# 01_MCU_DSP.net
KiCad netlist of a schematic drawn in Altium Designer
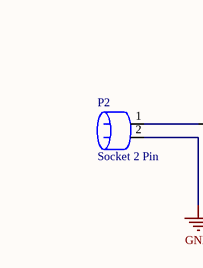
[diagram p0: 01_MCU_DSP..SchDoc, bottom left]
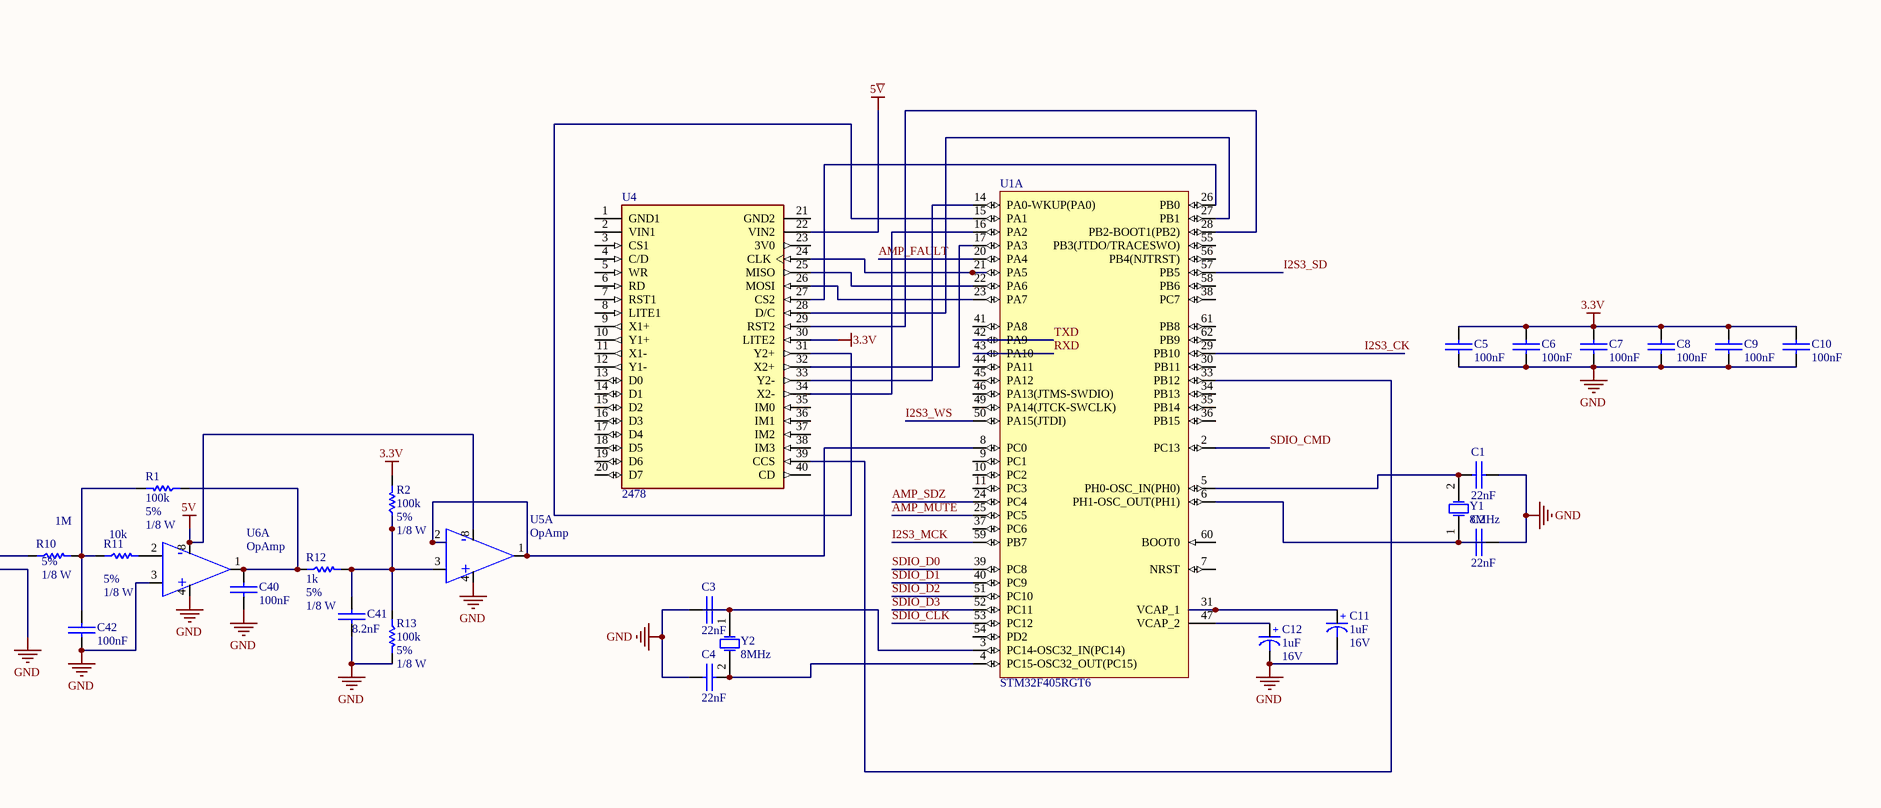
[diagram p1: 01_MCU_DSP..SchDoc, bottom right]

(export (version "E")
  (design (tool "Eeschema 10.0.6"))
  (components
    (comp (ref "C1")
      (value "22nF")
      (footprint "SMD_CAP_1206")
      (description "Bipolar Capacitor")
      (fields (field (name "VOLTAGE") "100V") (field (name "DESIGNER") "Saeid Jorablo"))
      (libsource (lib "My Library") (part "Cap-Bipolar"))
    )
    (comp (ref "C2")
      (value "22nF")
      (footprint "SMD_CAP_1206")
      (description "Bipolar Capacitor")
      (fields (field (name "VOLTAGE") "100V") (field (name "DESIGNER") "Saeid Jorablo"))
      (libsource (lib "My Library") (part "Cap-Bipolar"))
    )
    (comp (ref "C3")
      (value "22nF")
      (footprint "SMD_CAP_1206")
      (description "Bipolar Capacitor")
      (fields (field (name "VOLTAGE") "100V") (field (name "DESIGNER") "Saeid Jorablo"))
      (libsource (lib "My Library") (part "Cap-Bipolar"))
    )
    (comp (ref "C4")
      (value "22nF")
      (footprint "SMD_CAP_1206")
      (description "Bipolar Capacitor")
      (fields (field (name "VOLTAGE") "100V") (field (name "DESIGNER") "Saeid Jorablo"))
      (libsource (lib "My Library") (part "Cap-Bipolar"))
    )
    (comp (ref "C5")
      (value "100nF")
      (footprint "SMD_CAP_1206")
      (description "Bipolar Capacitor")
      (fields (field (name "VOLTAGE") "100V") (field (name "DESIGNER") "Saeid Jorablo"))
      (libsource (lib "My Library") (part "Cap-Bipolar"))
    )
    (comp (ref "C6")
      (value "100nF")
      (footprint "SMD_CAP_1206")
      (description "Bipolar Capacitor")
      (fields (field (name "VOLTAGE") "100V") (field (name "DESIGNER") "Saeid Jorablo"))
      (libsource (lib "My Library") (part "Cap-Bipolar"))
    )
    (comp (ref "C7")
      (value "100nF")
      (footprint "SMD_CAP_1206")
      (description "Bipolar Capacitor")
      (fields (field (name "VOLTAGE") "100V") (field (name "DESIGNER") "Saeid Jorablo"))
      (libsource (lib "My Library") (part "Cap-Bipolar"))
    )
    (comp (ref "C8")
      (value "100nF")
      (footprint "SMD_CAP_1206")
      (description "Bipolar Capacitor")
      (fields (field (name "VOLTAGE") "100V") (field (name "DESIGNER") "Saeid Jorablo"))
      (libsource (lib "My Library") (part "Cap-Bipolar"))
    )
    (comp (ref "C9")
      (value "100nF")
      (footprint "SMD_CAP_1206")
      (description "Bipolar Capacitor")
      (fields (field (name "VOLTAGE") "100V") (field (name "DESIGNER") "Saeid Jorablo"))
      (libsource (lib "My Library") (part "Cap-Bipolar"))
    )
    (comp (ref "C10")
      (value "100nF")
      (footprint "SMD_CAP_1206")
      (description "Bipolar Capacitor")
      (fields (field (name "VOLTAGE") "100V") (field (name "DESIGNER") "Saeid Jorablo"))
      (libsource (lib "My Library") (part "Cap-Bipolar"))
    )
    (comp (ref "C11")
      (value "1uF")
      (footprint "cap 01")
      (description "Polar Capacitor")
      (fields (field (name "VOLTAGE") "16V") (field (name "DESIGNER") "Saeid Jorablo"))
      (libsource (lib "My Library") (part "Cap-Polar"))
    )
    (comp (ref "C12")
      (value "1uF")
      (footprint "cap 01")
      (description "Polar Capacitor")
      (fields (field (name "VOLTAGE") "16V") (field (name "DESIGNER") "Saeid Jorablo"))
      (libsource (lib "My Library") (part "Cap-Polar"))
    )
    (comp (ref "C40")
      (value "100nF")
      (footprint "SMD_CAP_1206")
      (description "Bipolar Capacitor")
      (fields (field (name "VOLTAGE") "100V") (field (name "DESIGNER") "Saeid Jorablo"))
      (libsource (lib "My Library") (part "Cap-Bipolar"))
    )
    (comp (ref "C41")
      (value "8.2nF")
      (footprint "SMD_CAP_1206")
      (description "Bipolar Capacitor")
      (fields (field (name "VOLTAGE") "100V") (field (name "DESIGNER") "Saeid Jorablo"))
      (libsource (lib "My Library") (part "Cap-Bipolar"))
    )
    (comp (ref "C42")
      (value "100nF")
      (footprint "SMD_CAP_1206")
      (description "Bipolar Capacitor")
      (fields (field (name "VOLTAGE") "100V") (field (name "DESIGNER") "Saeid Jorablo"))
      (libsource (lib "My Library") (part "Cap-Bipolar"))
    )
    (comp (ref "P2")
      (value "Socket 2 Pin")
      (footprint "2pin")
      (description "Power Input")
      (libsource (lib "My Library") (part "Socket 2 Pin"))
    )
    (comp (ref "R1")
      (value "100k")
      (footprint "RES 0805 (2012X06L)")
      (description "Resistor")
      (fields (field (name "TOLERANCE") "5%") (field (name "POWER") "1/8 W"))
      (libsource (lib "My Library") (part "Resistor"))
    )
    (comp (ref "R2")
      (value "100k")
      (footprint "RES 0805 (2012X06L)")
      (description "Resistor")
      (fields (field (name "TOLERANCE") "5%") (field (name "POWER") "1/8 W"))
      (libsource (lib "My Library") (part "Resistor"))
    )
    (comp (ref "R10")
      (value "1M")
      (footprint "RES 0805 (2012X06L)")
      (description "Resistor")
      (fields (field (name "TOLERANCE") "5%") (field (name "POWER") "1/8 W"))
      (libsource (lib "My Library") (part "Resistor"))
    )
    (comp (ref "R11")
      (value "10k")
      (footprint "RES 0805 (2012X06L)")
      (description "Resistor")
      (fields (field (name "TOLERANCE") "5%") (field (name "POWER") "1/8 W"))
      (libsource (lib "My Library") (part "Resistor"))
    )
    (comp (ref "R12")
      (value "1k")
      (footprint "RES 0805 (2012X06L)")
      (description "Resistor")
      (fields (field (name "TOLERANCE") "5%") (field (name "POWER") "1/8 W"))
      (libsource (lib "My Library") (part "Resistor"))
    )
    (comp (ref "R13")
      (value "100k")
      (footprint "RES 0805 (2012X06L)")
      (description "Resistor")
      (fields (field (name "TOLERANCE") "5%") (field (name "POWER") "1/8 W"))
      (libsource (lib "My Library") (part "Resistor"))
    )
    (comp (ref "U1")
      (value "STM32F405RGT6")
      (footprint "STM-LQFP64_N")
      (fields (field (name "MANUFACTURER") "STMicroelectronics"))
      (libsource (lib "STMicroelectronics STM32 F4") (part "STM32F405RGT6"))
    )
    (comp (ref "U4")
      (value "2478")
      (footprint "ADAFRUIT_2478")
      (fields (field (name "MF") "Adafruit Industries"))
      (libsource (lib "2478") (part "2478"))
    )
    (comp (ref "U5")
      (value "OpAmp")
      (footprint "SOIC8-Narrow")
      (description "Dual Low Noise Operational Amplifier (OpAmp)")
      (libsource (lib "My Library") (part "OpAmp"))
    )
    (comp (ref "U6")
      (value "OpAmp")
      (footprint "SOIC8-Narrow")
      (description "Dual Low Noise Operational Amplifier (OpAmp)")
      (libsource (lib "My Library") (part "OpAmp"))
    )
    (comp (ref "Y1")
      (value "8MHz")
      (footprint "XTAL Small")
      (description "XTAL Crystal")
      (libsource (lib "My Library") (part "XTAL"))
    )
    (comp (ref "Y2")
      (value "8MHz")
      (footprint "XTAL Small")
      (description "XTAL Crystal")
      (libsource (lib "My Library") (part "XTAL"))
    )
  )
  (nets
    (net (code "1") (name "/AMP_FAULT") (class "Default")
      (node (ref "U1") (pin "20") (pinfunction "PA4_20") (pintype "bidirectional"))
    )
    (net (code "2") (name "/AMP_MUTE") (class "Default")
      (node (ref "U1") (pin "25") (pinfunction "PC5_25") (pintype "bidirectional"))
    )
    (net (code "3") (name "/AMP_SDZ") (class "Default")
      (node (ref "U1") (pin "24") (pinfunction "PC4_24") (pintype "bidirectional"))
    )
    (net (code "4") (name "/I2S3_CK") (class "Default")
      (node (ref "U1") (pin "29") (pinfunction "PB10_29") (pintype "bidirectional"))
    )
    (net (code "5") (name "/I2S3_MCK") (class "Default")
      (node (ref "U1") (pin "59") (pinfunction "PB7_59") (pintype "bidirectional"))
    )
    (net (code "6") (name "/I2S3_SD") (class "Default")
      (node (ref "U1") (pin "57") (pinfunction "PB5_57") (pintype "bidirectional"))
    )
    (net (code "7") (name "/I2S3_WS") (class "Default")
      (node (ref "U1") (pin "50") (pinfunction "PA15(JTDI)_50") (pintype "bidirectional"))
    )
    (net (code "8") (name "/RXD") (class "Default")
      (node (ref "U1") (pin "43") (pinfunction "PA10_43") (pintype "bidirectional"))
    )
    (net (code "9") (name "/SDIO_CLK") (class "Default")
      (node (ref "U1") (pin "53") (pinfunction "PC12_53") (pintype "bidirectional"))
    )
    (net (code "10") (name "/SDIO_CMD") (class "Default")
      (node (ref "U1") (pin "2") (pinfunction "PC13_2") (pintype "bidirectional"))
    )
    (net (code "11") (name "/SDIO_D0") (class "Default")
      (node (ref "U1") (pin "39") (pinfunction "PC8_39") (pintype "bidirectional"))
    )
    (net (code "12") (name "/SDIO_D1") (class "Default")
      (node (ref "U1") (pin "40") (pinfunction "PC9_40") (pintype "bidirectional"))
    )
    (net (code "13") (name "/SDIO_D2") (class "Default")
      (node (ref "U1") (pin "51") (pinfunction "PC10_51") (pintype "bidirectional"))
    )
    (net (code "14") (name "/SDIO_D3") (class "Default")
      (node (ref "U1") (pin "52") (pinfunction "PC11_52") (pintype "bidirectional"))
    )
    (net (code "15") (name "/TXD") (class "Default")
      (node (ref "U1") (pin "42") (pinfunction "PA9_42") (pintype "bidirectional"))
    )
    (net (code "16") (name "3.3V") (class "Default")
      (node (ref "C10") (pin "1") (pinfunction "+_1") (pintype "passive"))
      (node (ref "C5") (pin "1") (pinfunction "+_1") (pintype "passive"))
      (node (ref "C6") (pin "1") (pinfunction "+_1") (pintype "passive"))
      (node (ref "C7") (pin "1") (pinfunction "+_1") (pintype "passive"))
      (node (ref "C8") (pin "1") (pinfunction "+_1") (pintype "passive"))
      (node (ref "C9") (pin "1") (pinfunction "+_1") (pintype "passive"))
      (node (ref "R2") (pin "2") (pinfunction "2_2") (pintype "passive"))
      (node (ref "U4") (pin "30") (pinfunction "LITE2_30") (pintype "input"))
    )
    (net (code "17") (name "5V") (class "Default")
      (node (ref "U5") (pin "8") (pinfunction "V+_8") (pintype "passive"))
      (node (ref "U6") (pin "8") (pinfunction "V+_8") (pintype "passive"))
    )
    (net (code "18") (name "5~{V}") (class "Default")
      (node (ref "U4") (pin "22") (pinfunction "VIN2_22") (pintype "power_in"))
    )
    (net (code "19") (name "GND") (class "Default")
      (node (ref "C1") (pin "2") (pinfunction "-_2") (pintype "passive"))
      (node (ref "C10") (pin "2") (pinfunction "-_2") (pintype "passive"))
      (node (ref "C11") (pin "2") (pinfunction "-_2") (pintype "passive"))
      (node (ref "C12") (pin "2") (pinfunction "-_2") (pintype "passive"))
      (node (ref "C2") (pin "2") (pinfunction "-_2") (pintype "passive"))
      (node (ref "C3") (pin "2") (pinfunction "-_2") (pintype "passive"))
      (node (ref "C4") (pin "2") (pinfunction "-_2") (pintype "passive"))
      (node (ref "C40") (pin "2") (pinfunction "-_2") (pintype "passive"))
      (node (ref "C41") (pin "2") (pinfunction "-_2") (pintype "passive"))
      (node (ref "C42") (pin "2") (pinfunction "-_2") (pintype "passive"))
      (node (ref "C5") (pin "2") (pinfunction "-_2") (pintype "passive"))
      (node (ref "C6") (pin "2") (pinfunction "-_2") (pintype "passive"))
      (node (ref "C7") (pin "2") (pinfunction "-_2") (pintype "passive"))
      (node (ref "C8") (pin "2") (pinfunction "-_2") (pintype "passive"))
      (node (ref "C9") (pin "2") (pinfunction "-_2") (pintype "passive"))
      (node (ref "P2") (pin "2") (pinfunction "2_2") (pintype "passive"))
      (node (ref "R13") (pin "2") (pinfunction "2_2") (pintype "passive"))
      (node (ref "U5") (pin "4") (pinfunction "V-_4") (pintype "passive"))
      (node (ref "U6") (pin "3") (pinfunction "Noninverter_Input_3") (pintype "passive"))
      (node (ref "U6") (pin "4") (pinfunction "V-_4") (pintype "passive"))
    )
    (net (code "20") (name "Net-(C1-+)") (class "Default")
      (node (ref "C1") (pin "1") (pinfunction "+_1") (pintype "passive"))
      (node (ref "U1") (pin "5") (pinfunction "PH0-OSC_IN(PH0)_5") (pintype "bidirectional"))
      (node (ref "Y1") (pin "2") (pinfunction "OSC2_2") (pintype "passive"))
    )
    (net (code "21") (name "Net-(C2-+)") (class "Default")
      (node (ref "C2") (pin "1") (pinfunction "+_1") (pintype "passive"))
      (node (ref "U1") (pin "6") (pinfunction "PH1-OSC_OUT(PH1)_6") (pintype "bidirectional"))
      (node (ref "Y1") (pin "1") (pinfunction "OSC1_1") (pintype "passive"))
    )
    (net (code "22") (name "Net-(C3-+)") (class "Default")
      (node (ref "C3") (pin "1") (pinfunction "+_1") (pintype "passive"))
      (node (ref "U1") (pin "3") (pinfunction "PC14-OSC32_IN(PC14)_3") (pintype "bidirectional"))
      (node (ref "Y2") (pin "1") (pinfunction "OSC1_1") (pintype "passive"))
    )
    (net (code "23") (name "Net-(C4-+)") (class "Default")
      (node (ref "C4") (pin "1") (pinfunction "+_1") (pintype "passive"))
      (node (ref "U1") (pin "4") (pinfunction "PC15-OSC32_OUT(PC15)_4") (pintype "bidirectional"))
      (node (ref "Y2") (pin "2") (pinfunction "OSC2_2") (pintype "passive"))
    )
    (net (code "24") (name "Net-(C11-+)") (class "Default")
      (node (ref "C11") (pin "1") (pinfunction "+_1") (pintype "passive"))
      (node (ref "U1") (pin "31") (pinfunction "VCAP_1_31") (pintype "power_in"))
    )
    (net (code "25") (name "Net-(C12-+)") (class "Default")
      (node (ref "C12") (pin "1") (pinfunction "+_1") (pintype "passive"))
      (node (ref "U1") (pin "47") (pinfunction "VCAP_2_47") (pintype "power_in"))
    )
    (net (code "26") (name "Net-(C40-+)") (class "Default")
      (node (ref "C40") (pin "1") (pinfunction "+_1") (pintype "passive"))
      (node (ref "R1") (pin "1") (pinfunction "1_1") (pintype "passive"))
      (node (ref "R12") (pin "1") (pinfunction "1_1") (pintype "passive"))
      (node (ref "U6") (pin "1") (pinfunction "Output_1") (pintype "passive"))
    )
    (net (code "27") (name "Net-(C41-+)") (class "Default")
      (node (ref "C41") (pin "1") (pinfunction "+_1") (pintype "passive"))
      (node (ref "R12") (pin "2") (pinfunction "2_2") (pintype "passive"))
      (node (ref "R13") (pin "1") (pinfunction "1_1") (pintype "passive"))
      (node (ref "R2") (pin "1") (pinfunction "1_1") (pintype "passive"))
      (node (ref "U5") (pin "3") (pinfunction "Noninverter_Input_3") (pintype "passive"))
    )
    (net (code "28") (name "Net-(C42-+)") (class "Default")
      (node (ref "C42") (pin "1") (pinfunction "+_1") (pintype "passive"))
      (node (ref "R1") (pin "2") (pinfunction "2_2") (pintype "passive"))
      (node (ref "R10") (pin "2") (pinfunction "2_2") (pintype "passive"))
      (node (ref "R11") (pin "1") (pinfunction "1_1") (pintype "passive"))
    )
    (net (code "29") (name "Net-(P2-Pad1)") (class "Default")
      (node (ref "P2") (pin "1") (pinfunction "1_1") (pintype "passive"))
      (node (ref "R10") (pin "1") (pinfunction "1_1") (pintype "passive"))
    )
    (net (code "30") (name "Net-(U1A-PA0-WKUP(PA0))") (class "Default")
      (node (ref "U1") (pin "14") (pinfunction "PA0-WKUP(PA0)_14") (pintype "bidirectional"))
      (node (ref "U4") (pin "33") (pinfunction "Y2-_33") (pintype "output"))
    )
    (net (code "31") (name "Net-(U1A-PA1)") (class "Default")
      (node (ref "U1") (pin "15") (pinfunction "PA1_15") (pintype "bidirectional"))
      (node (ref "U4") (pin "31") (pinfunction "Y2+_31") (pintype "output"))
    )
    (net (code "32") (name "Net-(U1A-PA2)") (class "Default")
      (node (ref "U1") (pin "16") (pinfunction "PA2_16") (pintype "bidirectional"))
      (node (ref "U4") (pin "34") (pinfunction "X2-_34") (pintype "output"))
    )
    (net (code "33") (name "Net-(U1A-PA3)") (class "Default")
      (node (ref "U1") (pin "17") (pinfunction "PA3_17") (pintype "bidirectional"))
      (node (ref "U4") (pin "32") (pinfunction "X2+_32") (pintype "output"))
    )
    (net (code "34") (name "Net-(U1A-PA5)") (class "Default")
      (node (ref "U1") (pin "21") (pinfunction "PA5_21") (pintype "bidirectional"))
      (node (ref "U4") (pin "24") (pinfunction "CLK_24") (pintype "input"))
    )
    (net (code "35") (name "Net-(U1A-PA6)") (class "Default")
      (node (ref "U1") (pin "22") (pinfunction "PA6_22") (pintype "bidirectional"))
      (node (ref "U4") (pin "25") (pinfunction "MISO_25") (pintype "output"))
    )
    (net (code "36") (name "Net-(U1A-PA7)") (class "Default")
      (node (ref "U1") (pin "23") (pinfunction "PA7_23") (pintype "bidirectional"))
      (node (ref "U4") (pin "26") (pinfunction "MOSI_26") (pintype "input"))
    )
    (net (code "37") (name "Net-(U1A-PB0)") (class "Default")
      (node (ref "U1") (pin "26") (pinfunction "PB0_26") (pintype "bidirectional"))
      (node (ref "U4") (pin "27") (pinfunction "CS2_27") (pintype "input"))
    )
    (net (code "38") (name "Net-(U1A-PB1)") (class "Default")
      (node (ref "U1") (pin "27") (pinfunction "PB1_27") (pintype "bidirectional"))
      (node (ref "U4") (pin "28") (pinfunction "D/C_28") (pintype "input"))
    )
    (net (code "39") (name "Net-(U1A-PB2-BOOT1(PB2))") (class "Default")
      (node (ref "U1") (pin "28") (pinfunction "PB2-BOOT1(PB2)_28") (pintype "bidirectional"))
      (node (ref "U4") (pin "29") (pinfunction "RST2_29") (pintype "input"))
    )
    (net (code "40") (name "Net-(U1A-PB12)") (class "Default")
      (node (ref "U1") (pin "33") (pinfunction "PB12_33") (pintype "bidirectional"))
      (node (ref "U4") (pin "39") (pinfunction "CCS_39") (pintype "input"))
    )
    (net (code "41") (name "Net-(U1A-PC0)") (class "Default")
      (node (ref "U1") (pin "8") (pinfunction "PC0_8") (pintype "bidirectional"))
      (node (ref "U5") (pin "1") (pinfunction "Output_1") (pintype "passive"))
      (node (ref "U5") (pin "2") (pinfunction "Inverter_Input_2") (pintype "passive"))
    )
    (net (code "42") (name "Net-(U6A-Inverter_Input)") (class "Default")
      (node (ref "R11") (pin "2") (pinfunction "2_2") (pintype "passive"))
      (node (ref "U6") (pin "2") (pinfunction "Inverter_Input_2") (pintype "passive"))
    )
    (net (code "43") (name "unconnected-(U1A-BOOT0-Pad60)") (class "Default")
      (node (ref "U1") (pin "60") (pinfunction "BOOT0_60") (pintype "input"))
    )
    (net (code "44") (name "unconnected-(U1A-NRST-Pad7)") (class "Default")
      (node (ref "U1") (pin "7") (pinfunction "NRST_7") (pintype "bidirectional"))
    )
    (net (code "45") (name "unconnected-(U1A-PA8-Pad41)") (class "Default")
      (node (ref "U1") (pin "41") (pinfunction "PA8_41") (pintype "bidirectional"))
    )
    (net (code "46") (name "unconnected-(U1A-PA11-Pad44)") (class "Default")
      (node (ref "U1") (pin "44") (pinfunction "PA11_44") (pintype "bidirectional"))
    )
    (net (code "47") (name "unconnected-(U1A-PA12-Pad45)") (class "Default")
      (node (ref "U1") (pin "45") (pinfunction "PA12_45") (pintype "bidirectional"))
    )
    (net (code "48") (name "unconnected-(U1A-PA13(JTMS-SWDIO)-Pad46)") (class "Default")
      (node (ref "U1") (pin "46") (pinfunction "PA13(JTMS-SWDIO)_46") (pintype "bidirectional"))
    )
    (net (code "49") (name "unconnected-(U1A-PA14(JTCK-SWCLK)-Pad49)") (class "Default")
      (node (ref "U1") (pin "49") (pinfunction "PA14(JTCK-SWCLK)_49") (pintype "bidirectional"))
    )
    (net (code "50") (name "unconnected-(U1A-PB3(JTDO{slash}TRACESWO)-Pad55)") (class "Default")
      (node (ref "U1") (pin "55") (pinfunction "PB3(JTDO/TRACESWO)_55") (pintype "bidirectional"))
    )
    (net (code "51") (name "unconnected-(U1A-PB4(NJTRST)-Pad56)") (class "Default")
      (node (ref "U1") (pin "56") (pinfunction "PB4(NJTRST)_56") (pintype "bidirectional"))
    )
    (net (code "52") (name "unconnected-(U1A-PB6-Pad58)") (class "Default")
      (node (ref "U1") (pin "58") (pinfunction "PB6_58") (pintype "bidirectional"))
    )
    (net (code "53") (name "unconnected-(U1A-PB8-Pad61)") (class "Default")
      (node (ref "U1") (pin "61") (pinfunction "PB8_61") (pintype "bidirectional"))
    )
    (net (code "54") (name "unconnected-(U1A-PB9-Pad62)") (class "Default")
      (node (ref "U1") (pin "62") (pinfunction "PB9_62") (pintype "bidirectional"))
    )
    (net (code "55") (name "unconnected-(U1A-PB11-Pad30)") (class "Default")
      (node (ref "U1") (pin "30") (pinfunction "PB11_30") (pintype "bidirectional"))
    )
    (net (code "56") (name "unconnected-(U1A-PB13-Pad34)") (class "Default")
      (node (ref "U1") (pin "34") (pinfunction "PB13_34") (pintype "bidirectional"))
    )
    (net (code "57") (name "unconnected-(U1A-PB14-Pad35)") (class "Default")
      (node (ref "U1") (pin "35") (pinfunction "PB14_35") (pintype "bidirectional"))
    )
    (net (code "58") (name "unconnected-(U1A-PB15-Pad36)") (class "Default")
      (node (ref "U1") (pin "36") (pinfunction "PB15_36") (pintype "bidirectional"))
    )
    (net (code "59") (name "unconnected-(U1A-PC1-Pad9)") (class "Default")
      (node (ref "U1") (pin "9") (pinfunction "PC1_9") (pintype "bidirectional"))
    )
    (net (code "60") (name "unconnected-(U1A-PC2-Pad10)") (class "Default")
      (node (ref "U1") (pin "10") (pinfunction "PC2_10") (pintype "bidirectional"))
    )
    (net (code "61") (name "unconnected-(U1A-PC3-Pad11)") (class "Default")
      (node (ref "U1") (pin "11") (pinfunction "PC3_11") (pintype "bidirectional"))
    )
    (net (code "62") (name "unconnected-(U1A-PC6-Pad37)") (class "Default")
      (node (ref "U1") (pin "37") (pinfunction "PC6_37") (pintype "bidirectional"))
    )
    (net (code "63") (name "unconnected-(U1A-PC7-Pad38)") (class "Default")
      (node (ref "U1") (pin "38") (pinfunction "PC7_38") (pintype "bidirectional"))
    )
    (net (code "64") (name "unconnected-(U1A-PD2-Pad54)") (class "Default")
      (node (ref "U1") (pin "54") (pinfunction "PD2_54") (pintype "bidirectional"))
    )
    (net (code "65") (name "unconnected-(U4-3V0-Pad23)") (class "Default")
      (node (ref "U4") (pin "23") (pinfunction "3V0_23") (pintype "output"))
    )
    (net (code "66") (name "unconnected-(U4-CD-Pad40)") (class "Default")
      (node (ref "U4") (pin "40") (pinfunction "CD_40") (pintype "output"))
    )
    (net (code "67") (name "unconnected-(U4-CS1-Pad3)") (class "Default")
      (node (ref "U4") (pin "3") (pinfunction "CS1_3") (pintype "input"))
    )
    (net (code "68") (name "unconnected-(U4-C{slash}D-Pad4)") (class "Default")
      (node (ref "U4") (pin "4") (pinfunction "C/D_4") (pintype "input"))
    )
    (net (code "69") (name "unconnected-(U4-D0-Pad13)") (class "Default")
      (node (ref "U4") (pin "13") (pinfunction "D0_13") (pintype "bidirectional"))
    )
    (net (code "70") (name "unconnected-(U4-D1-Pad14)") (class "Default")
      (node (ref "U4") (pin "14") (pinfunction "D1_14") (pintype "bidirectional"))
    )
    (net (code "71") (name "unconnected-(U4-D2-Pad15)") (class "Default")
      (node (ref "U4") (pin "15") (pinfunction "D2_15") (pintype "bidirectional"))
    )
    (net (code "72") (name "unconnected-(U4-D3-Pad16)") (class "Default")
      (node (ref "U4") (pin "16") (pinfunction "D3_16") (pintype "bidirectional"))
    )
    (net (code "73") (name "unconnected-(U4-D4-Pad17)") (class "Default")
      (node (ref "U4") (pin "17") (pinfunction "D4_17") (pintype "bidirectional"))
    )
    (net (code "74") (name "unconnected-(U4-D5-Pad18)") (class "Default")
      (node (ref "U4") (pin "18") (pinfunction "D5_18") (pintype "bidirectional"))
    )
    (net (code "75") (name "unconnected-(U4-D6-Pad19)") (class "Default")
      (node (ref "U4") (pin "19") (pinfunction "D6_19") (pintype "bidirectional"))
    )
    (net (code "76") (name "unconnected-(U4-D7-Pad20)") (class "Default")
      (node (ref "U4") (pin "20") (pinfunction "D7_20") (pintype "bidirectional"))
    )
    (net (code "77") (name "unconnected-(U4-GND1-Pad1)") (class "Default")
      (node (ref "U4") (pin "1") (pinfunction "GND1_1") (pintype "power_in"))
    )
    (net (code "78") (name "unconnected-(U4-GND2-Pad21)") (class "Default")
      (node (ref "U4") (pin "21") (pinfunction "GND2_21") (pintype "power_in"))
    )
    (net (code "79") (name "unconnected-(U4-IM0-Pad35)") (class "Default")
      (node (ref "U4") (pin "35") (pinfunction "IM0_35") (pintype "input"))
    )
    (net (code "80") (name "unconnected-(U4-IM1-Pad36)") (class "Default")
      (node (ref "U4") (pin "36") (pinfunction "IM1_36") (pintype "input"))
    )
    (net (code "81") (name "unconnected-(U4-IM2-Pad37)") (class "Default")
      (node (ref "U4") (pin "37") (pinfunction "IM2_37") (pintype "input"))
    )
    (net (code "82") (name "unconnected-(U4-IM3-Pad38)") (class "Default")
      (node (ref "U4") (pin "38") (pinfunction "IM3_38") (pintype "input"))
    )
    (net (code "83") (name "unconnected-(U4-LITE1-Pad8)") (class "Default")
      (node (ref "U4") (pin "8") (pinfunction "LITE1_8") (pintype "input"))
    )
    (net (code "84") (name "unconnected-(U4-RD-Pad6)") (class "Default")
      (node (ref "U4") (pin "6") (pinfunction "RD_6") (pintype "input"))
    )
    (net (code "85") (name "unconnected-(U4-RST1-Pad7)") (class "Default")
      (node (ref "U4") (pin "7") (pinfunction "RST1_7") (pintype "input"))
    )
    (net (code "86") (name "unconnected-(U4-VIN1-Pad2)") (class "Default")
      (node (ref "U4") (pin "2") (pinfunction "VIN1_2") (pintype "power_in"))
    )
    (net (code "87") (name "unconnected-(U4-WR-Pad5)") (class "Default")
      (node (ref "U4") (pin "5") (pinfunction "WR_5") (pintype "input"))
    )
    (net (code "88") (name "unconnected-(U4-X1+-Pad9)") (class "Default")
      (node (ref "U4") (pin "9") (pinfunction "X1+_9") (pintype "output"))
    )
    (net (code "89") (name "unconnected-(U4-X1--Pad11)") (class "Default")
      (node (ref "U4") (pin "11") (pinfunction "X1-_11") (pintype "output"))
    )
    (net (code "90") (name "unconnected-(U4-Y1+-Pad10)") (class "Default")
      (node (ref "U4") (pin "10") (pinfunction "Y1+_10") (pintype "output"))
    )
    (net (code "91") (name "unconnected-(U4-Y1--Pad12)") (class "Default")
      (node (ref "U4") (pin "12") (pinfunction "Y1-_12") (pintype "output"))
    )
  )
)
